# Vinduino-GW-29-2-16.net
KiCad netlist of a schematic drawn in EAGLE
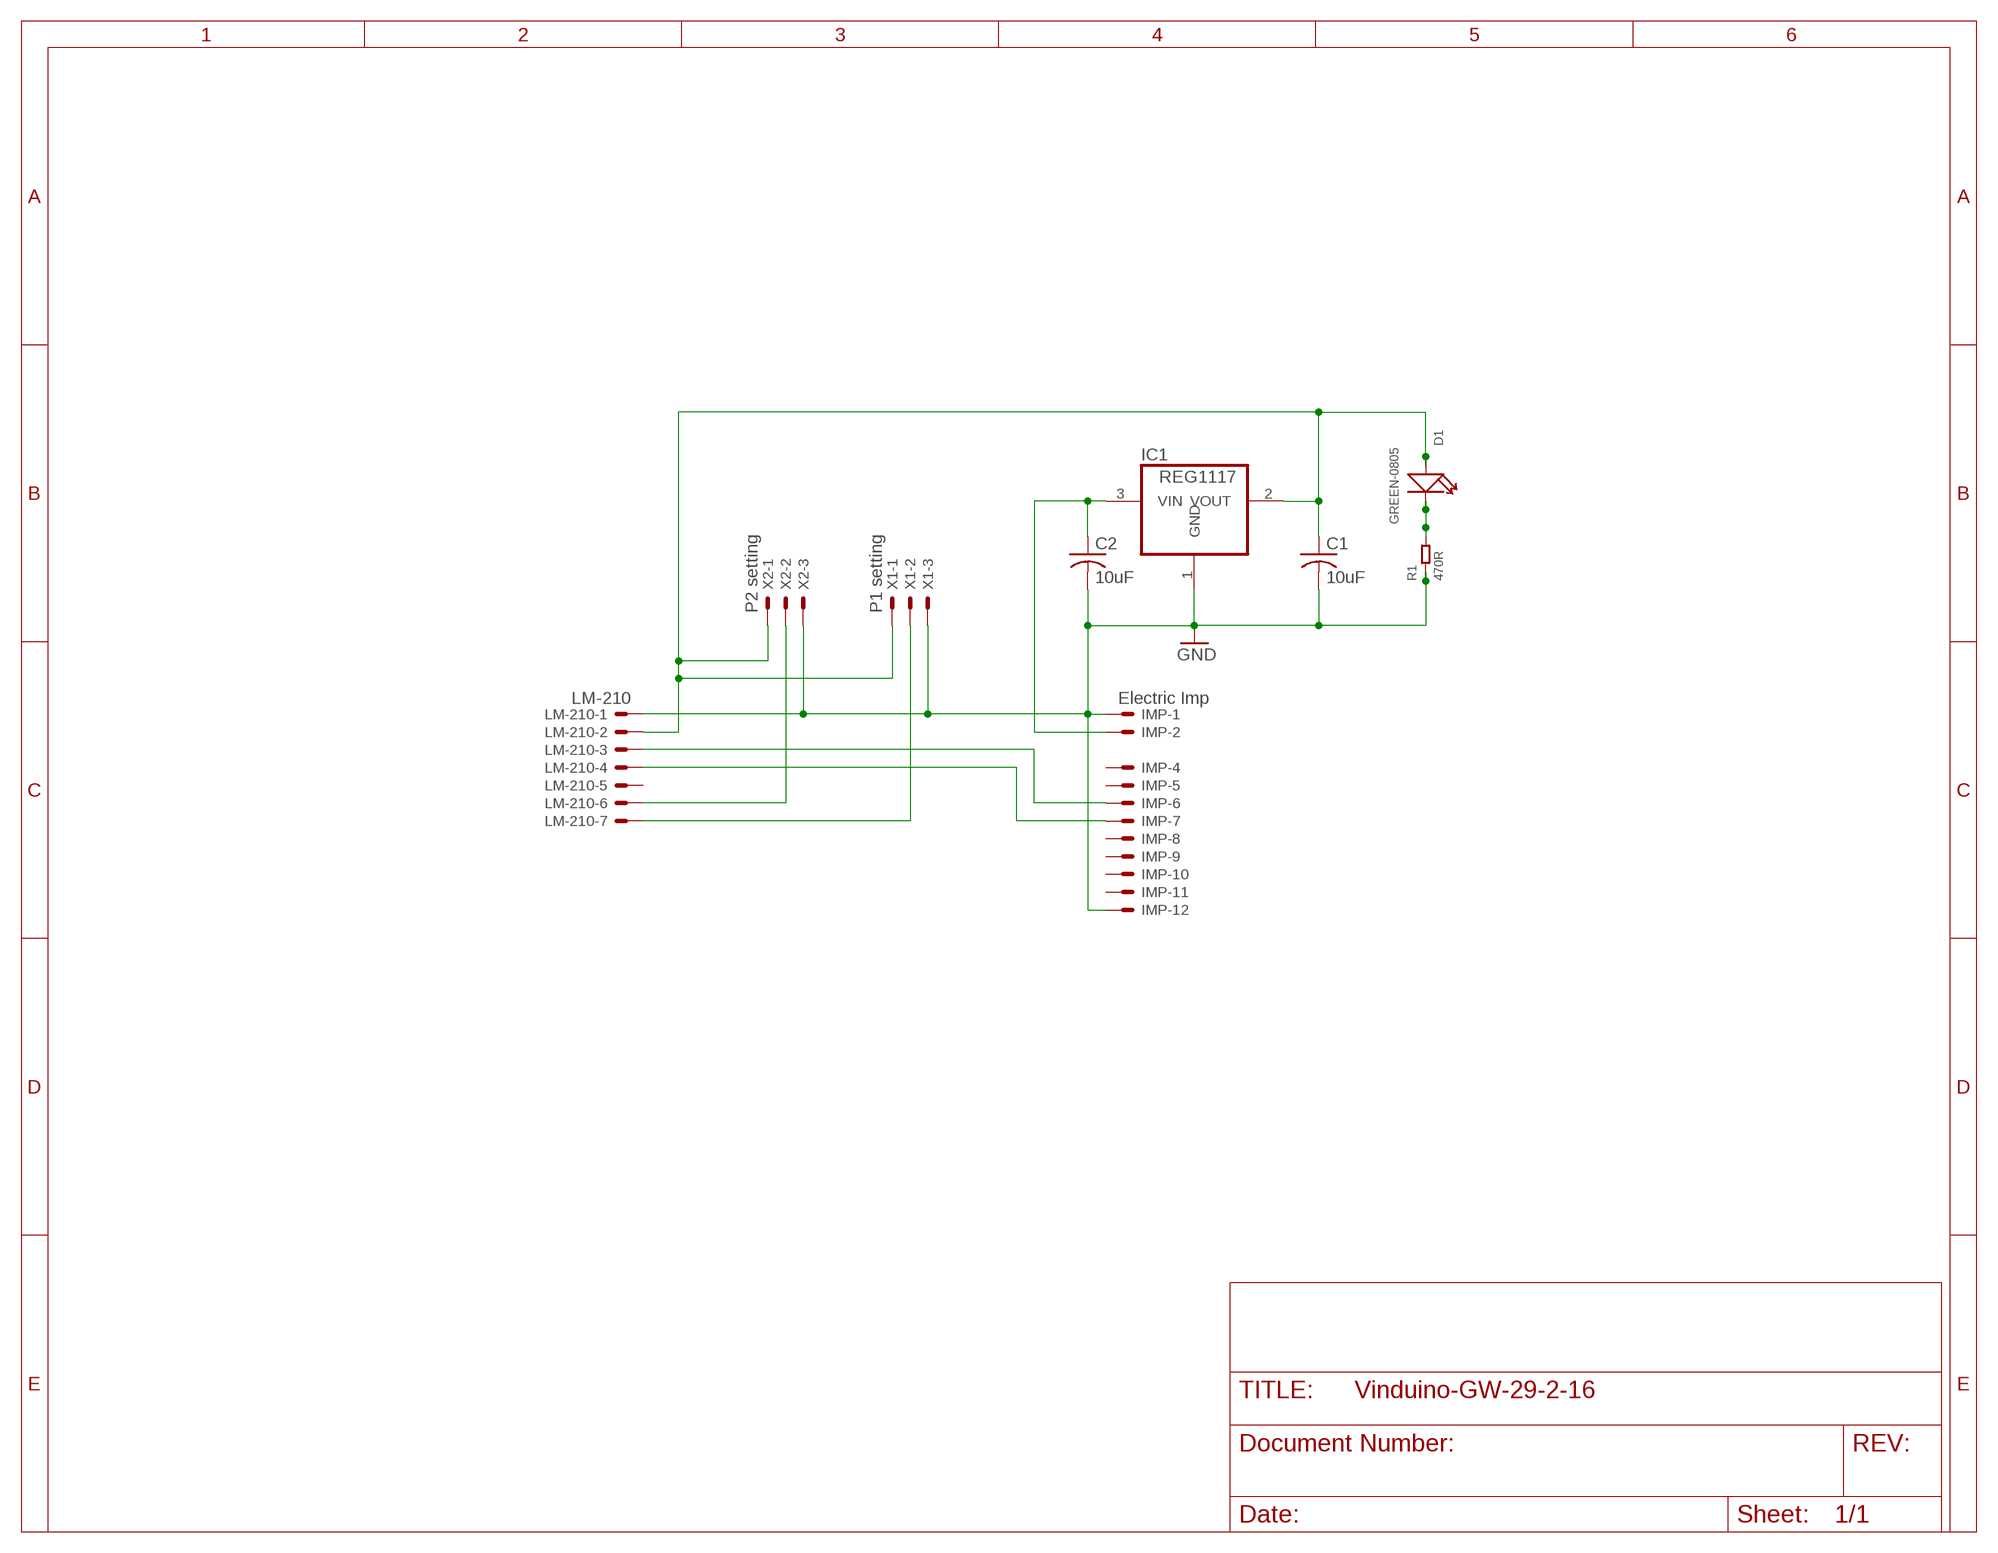
[diagram p0: schematic, sheet 1]

(export (version "E")
  (design (tool "Eeschema 10.0.6"))
  (components
    (comp (ref "C1")
      (value "10uF")
      (footprint "eagle-import:C025-030X050")
      (libsource (lib "eagle-import") (part "C-US025-030X050"))
    )
    (comp (ref "C2")
      (value "10uF")
      (footprint "eagle-import:C025-030X050")
      (libsource (lib "eagle-import") (part "C-US025-030X050"))
    )
    (comp (ref "D1")
      (value "GREEN-0805")
      (footprint "eagle-import:LED-0805")
      (fields (field (name "MPN") "17-215SYGC/S530-E2/TR8"))
      (libsource (lib "eagle-import") (part "SMD-LED-CLEAR-GREEN(0805)"))
    )
    (comp (ref "IC1")
      (value "REG1117")
      (footprint "eagle-import:SOT223")
      (libsource (lib "eagle-import") (part "REG1117"))
    )
    (comp (ref "IMP")
      (value "Electric Imp")
      (footprint "eagle-import:22-23-2121")
      (fields (field (name "MF") "MOLEX") (field (name "MPN") "22-23-2121"))
      (libsource (lib "eagle-import") (part "22-23-2121"))
    )
    (comp (ref "LM-210")
      (value "LM-210")
      (footprint "eagle-import:22-23-2071")
      (fields (field (name "MF") "MOLEX") (field (name "MPN") "22-23-2071"))
      (libsource (lib "eagle-import") (part "22-23-2071"))
    )
    (comp (ref "R1")
      (value "470R")
      (footprint "eagle-import:R0805")
      (fields (field (name "MPN") "RC0805FR-07470RL"))
      (libsource (lib "eagle-import") (part "SMD-RES-470R-1%-1/8W(0805)"))
    )
    (comp (ref "X1")
      (value "P1 setting")
      (footprint "eagle-import:22-23-2031")
      (fields (field (name "MF") "MOLEX") (field (name "MPN") "22-23-2031"))
      (libsource (lib "eagle-import") (part "22-23-2031"))
    )
    (comp (ref "X2")
      (value "P2 setting")
      (footprint "eagle-import:22-23-2031")
      (fields (field (name "MF") "MOLEX") (field (name "MPN") "22-23-2031"))
      (libsource (lib "eagle-import") (part "22-23-2031"))
    )
  )
  (nets
    (net (code "1") (name "GND") (class "Default")
      (node (ref "C1") (pin "2") (pinfunction "2_2") (pintype "passive"))
      (node (ref "C2") (pin "2") (pinfunction "2_2") (pintype "passive"))
      (node (ref "IC1") (pin "1") (pinfunction "GND_1") (pintype "power_in"))
      (node (ref "IMP") (pin "1") (pinfunction "S_1") (pintype "passive"))
      (node (ref "IMP") (pin "12") (pinfunction "S_12") (pintype "passive"))
      (node (ref "LM-210") (pin "1") (pinfunction "S_1") (pintype "passive"))
      (node (ref "R1") (pin "1") (pinfunction "1_1") (pintype "passive"))
      (node (ref "X1") (pin "3") (pinfunction "S_3") (pintype "passive"))
      (node (ref "X2") (pin "3") (pinfunction "S_3") (pintype "passive"))
    )
    (net (code "2") (name "Net-(D1-Pad-)") (class "Default")
      (node (ref "D1") (pin "-") (pinfunction "-_-") (pintype "passive"))
      (node (ref "R1") (pin "2") (pinfunction "2_2") (pintype "passive"))
    )
    (net (code "3") (name "Net-(IC1-VIN)") (class "Default")
      (node (ref "C2") (pin "1") (pinfunction "1_1") (pintype "passive"))
      (node (ref "IC1") (pin "3") (pinfunction "VIN_3") (pintype "input"))
      (node (ref "IMP") (pin "2") (pinfunction "S_2") (pintype "passive"))
    )
    (net (code "4") (name "Net-(IC1-VOUT)") (class "Default")
      (node (ref "C1") (pin "1") (pinfunction "1_1") (pintype "passive"))
      (node (ref "D1") (pin "+") (pinfunction "+_+") (pintype "passive"))
      (node (ref "IC1") (pin "2") (pinfunction "VOUT_2") (pintype "output"))
      (node (ref "LM-210") (pin "2") (pinfunction "S_2") (pintype "passive"))
      (node (ref "X1") (pin "1") (pinfunction "S_1") (pintype "passive"))
      (node (ref "X2") (pin "1") (pinfunction "S_1") (pintype "passive"))
    )
    (net (code "5") (name "Net-(IMPI-S)") (class "Default")
      (node (ref "IMP") (pin "6") (pinfunction "S_6") (pintype "passive"))
      (node (ref "LM-210") (pin "3") (pinfunction "S_3") (pintype "passive"))
    )
    (net (code "6") (name "Net-(IMPJ-S)") (class "Default")
      (node (ref "IMP") (pin "7") (pinfunction "S_7") (pintype "passive"))
      (node (ref "LM-210") (pin "4") (pinfunction "S_4") (pintype "passive"))
    )
    (net (code "7") (name "Net-(LM-210F-S)") (class "Default")
      (node (ref "LM-210") (pin "6") (pinfunction "S_6") (pintype "passive"))
      (node (ref "X2") (pin "2") (pinfunction "S_2") (pintype "passive"))
    )
    (net (code "8") (name "Net-(LM-210G-S)") (class "Default")
      (node (ref "LM-210") (pin "7") (pinfunction "S_7") (pintype "passive"))
      (node (ref "X1") (pin "2") (pinfunction "S_2") (pintype "passive"))
    )
    (net (code "9") (name "unconnected-(IMPB-S-Pad10)") (class "Default")
      (node (ref "IMP") (pin "10") (pinfunction "S_10") (pintype "passive"))
    )
    (net (code "10") (name "unconnected-(IMPC-S-Pad11)") (class "Default")
      (node (ref "IMP") (pin "11") (pinfunction "S_11") (pintype "passive"))
    )
    (net (code "11") (name "unconnected-(IMPG-S-Pad4)") (class "Default")
      (node (ref "IMP") (pin "4") (pinfunction "S_4") (pintype "passive"))
    )
    (net (code "12") (name "unconnected-(IMPH-S-Pad5)") (class "Default")
      (node (ref "IMP") (pin "5") (pinfunction "S_5") (pintype "passive"))
    )
    (net (code "13") (name "unconnected-(IMPK-S-Pad8)") (class "Default")
      (node (ref "IMP") (pin "8") (pinfunction "S_8") (pintype "passive"))
    )
    (net (code "14") (name "unconnected-(IMPL-S-Pad9)") (class "Default")
      (node (ref "IMP") (pin "9") (pinfunction "S_9") (pintype "passive"))
    )
    (net (code "15") (name "unconnected-(LM-210E-S-Pad5)") (class "Default")
      (node (ref "LM-210") (pin "5") (pinfunction "S_5") (pintype "passive"))
    )
  )
)
